# 1_0.net
KiCad netlist of a schematic drawn in EAGLE
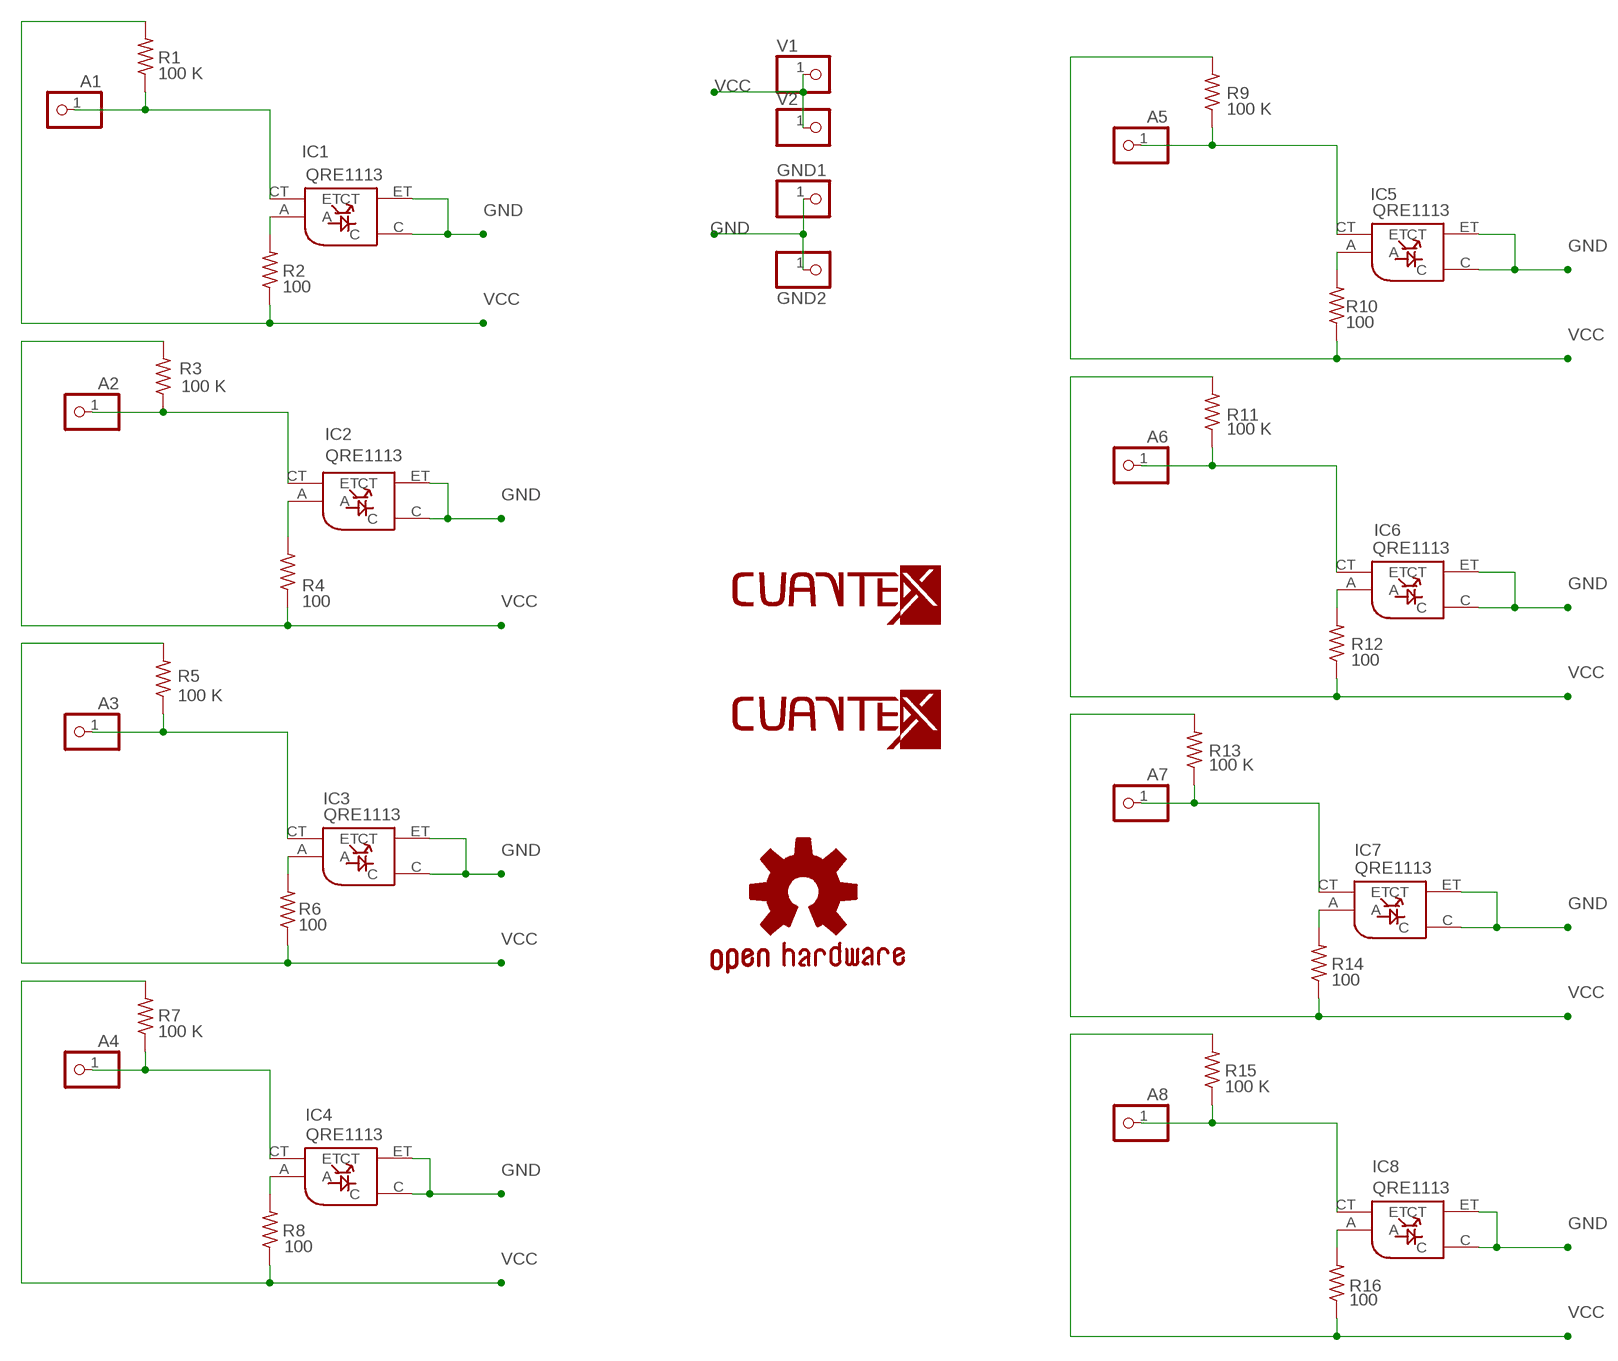
[diagram p0: schematic, sheet 1]

(export (version "E")
  (design (tool "Eeschema 10.0.6"))
  (components
    (comp (ref "A1")
      (value "PINHD-1X1")
      (footprint "eagle-import:1X01")
      (libsource (lib "eagle-import") (part "PINHD-1X1"))
    )
    (comp (ref "A2")
      (value "PINHD-1X1")
      (footprint "eagle-import:1X01")
      (libsource (lib "eagle-import") (part "PINHD-1X1"))
    )
    (comp (ref "A3")
      (value "PINHD-1X1")
      (footprint "eagle-import:1X01")
      (libsource (lib "eagle-import") (part "PINHD-1X1"))
    )
    (comp (ref "A4")
      (value "PINHD-1X1")
      (footprint "eagle-import:1X01")
      (libsource (lib "eagle-import") (part "PINHD-1X1"))
    )
    (comp (ref "A5")
      (value "PINHD-1X1")
      (footprint "eagle-import:1X01")
      (libsource (lib "eagle-import") (part "PINHD-1X1"))
    )
    (comp (ref "A6")
      (value "PINHD-1X1")
      (footprint "eagle-import:1X01")
      (libsource (lib "eagle-import") (part "PINHD-1X1"))
    )
    (comp (ref "A7")
      (value "PINHD-1X1")
      (footprint "eagle-import:1X01")
      (libsource (lib "eagle-import") (part "PINHD-1X1"))
    )
    (comp (ref "A8")
      (value "PINHD-1X1")
      (footprint "eagle-import:1X01")
      (libsource (lib "eagle-import") (part "PINHD-1X1"))
    )
    (comp (ref "GND1")
      (value "PINHD-1X1")
      (footprint "eagle-import:1X01")
      (libsource (lib "eagle-import") (part "PINHD-1X1"))
    )
    (comp (ref "GND2")
      (value "PINHD-1X1")
      (footprint "eagle-import:1X01")
      (libsource (lib "eagle-import") (part "PINHD-1X1"))
    )
    (comp (ref "GOLD_ORB_SM1")
      (value "OSHWLOGO_GOLD_ORB_SM")
      (footprint "eagle-import:OSHW2")
      (libsource (lib "eagle-import") (part "OSHWLOGO_GOLD_ORB_SM"))
    )
    (comp (ref "IC1")
      (value "QRE1113")
      (footprint "eagle-import:QRE1113")
      (libsource (lib "eagle-import") (part "QRE1113"))
    )
    (comp (ref "IC2")
      (value "QRE1113")
      (footprint "eagle-import:QRE1113")
      (libsource (lib "eagle-import") (part "QRE1113"))
    )
    (comp (ref "IC3")
      (value "QRE1113")
      (footprint "eagle-import:QRE1113")
      (libsource (lib "eagle-import") (part "QRE1113"))
    )
    (comp (ref "IC4")
      (value "QRE1113")
      (footprint "eagle-import:QRE1113")
      (libsource (lib "eagle-import") (part "QRE1113"))
    )
    (comp (ref "IC5")
      (value "QRE1113")
      (footprint "eagle-import:QRE1113")
      (libsource (lib "eagle-import") (part "QRE1113"))
    )
    (comp (ref "IC6")
      (value "QRE1113")
      (footprint "eagle-import:QRE1113")
      (libsource (lib "eagle-import") (part "QRE1113"))
    )
    (comp (ref "IC7")
      (value "QRE1113")
      (footprint "eagle-import:QRE1113")
      (libsource (lib "eagle-import") (part "QRE1113"))
    )
    (comp (ref "IC8")
      (value "QRE1113")
      (footprint "eagle-import:QRE1113")
      (libsource (lib "eagle-import") (part "QRE1113"))
    )
    (comp (ref "R1")
      (value "100 K")
      (footprint "eagle-import:R0603")
      (libsource (lib "eagle-import") (part "R-US_R0603"))
    )
    (comp (ref "R2")
      (value "100")
      (footprint "eagle-import:R0603")
      (libsource (lib "eagle-import") (part "R-US_R0603"))
    )
    (comp (ref "R3")
      (value "100 K")
      (footprint "eagle-import:R0603")
      (libsource (lib "eagle-import") (part "R-US_R0603"))
    )
    (comp (ref "R4")
      (value "100")
      (footprint "eagle-import:R0603")
      (libsource (lib "eagle-import") (part "R-US_R0603"))
    )
    (comp (ref "R5")
      (value "100 K")
      (footprint "eagle-import:R0603")
      (libsource (lib "eagle-import") (part "R-US_R0603"))
    )
    (comp (ref "R6")
      (value "100")
      (footprint "eagle-import:R0603")
      (libsource (lib "eagle-import") (part "R-US_R0603"))
    )
    (comp (ref "R7")
      (value "100 K")
      (footprint "eagle-import:R0603")
      (libsource (lib "eagle-import") (part "R-US_R0603"))
    )
    (comp (ref "R8")
      (value "100")
      (footprint "eagle-import:R0603")
      (libsource (lib "eagle-import") (part "R-US_R0603"))
    )
    (comp (ref "R9")
      (value "100 K")
      (footprint "eagle-import:R0603")
      (libsource (lib "eagle-import") (part "R-US_R0603"))
    )
    (comp (ref "R10")
      (value "100")
      (footprint "eagle-import:R0603")
      (libsource (lib "eagle-import") (part "R-US_R0603"))
    )
    (comp (ref "R11")
      (value "100 K")
      (footprint "eagle-import:R0603")
      (libsource (lib "eagle-import") (part "R-US_R0603"))
    )
    (comp (ref "R12")
      (value "100")
      (footprint "eagle-import:R0603")
      (libsource (lib "eagle-import") (part "R-US_R0603"))
    )
    (comp (ref "R13")
      (value "100 K")
      (footprint "eagle-import:R0603")
      (libsource (lib "eagle-import") (part "R-US_R0603"))
    )
    (comp (ref "R14")
      (value "100")
      (footprint "eagle-import:R0603")
      (libsource (lib "eagle-import") (part "R-US_R0603"))
    )
    (comp (ref "R15")
      (value "100 K")
      (footprint "eagle-import:R0603")
      (libsource (lib "eagle-import") (part "R-US_R0603"))
    )
    (comp (ref "R16")
      (value "100")
      (footprint "eagle-import:R0603")
      (libsource (lib "eagle-import") (part "R-US_R0603"))
    )
    (comp (ref "U$1")
      (value "LOGO-TOP-30MM")
      (footprint "eagle-import:C-1")
      (libsource (lib "eagle-import") (part "LOGO-TOP-30MM"))
    )
    (comp (ref "U$2")
      (value "LOGO-TOP-20MM")
      (footprint "eagle-import:C-0")
      (libsource (lib "eagle-import") (part "LOGO-TOP-20MM"))
    )
    (comp (ref "V1")
      (value "PINHD-1X1")
      (footprint "eagle-import:1X01")
      (libsource (lib "eagle-import") (part "PINHD-1X1"))
    )
    (comp (ref "V2")
      (value "PINHD-1X1")
      (footprint "eagle-import:1X01")
      (libsource (lib "eagle-import") (part "PINHD-1X1"))
    )
  )
  (nets
    (net (code "1") (name "/GND") (class "Default")
      (node (ref "GND1") (pin "1") (pinfunction "1_1") (pintype "passive"))
      (node (ref "GND2") (pin "1") (pinfunction "1_1") (pintype "passive"))
      (node (ref "IC1") (pin "C") (pinfunction "C_C") (pintype "bidirectional"))
      (node (ref "IC1") (pin "ET") (pinfunction "CT_ET") (pintype "bidirectional"))
      (node (ref "IC2") (pin "C") (pinfunction "C_C") (pintype "bidirectional"))
      (node (ref "IC2") (pin "ET") (pinfunction "CT_ET") (pintype "bidirectional"))
      (node (ref "IC3") (pin "C") (pinfunction "C_C") (pintype "bidirectional"))
      (node (ref "IC3") (pin "ET") (pinfunction "CT_ET") (pintype "bidirectional"))
      (node (ref "IC4") (pin "C") (pinfunction "C_C") (pintype "bidirectional"))
      (node (ref "IC4") (pin "ET") (pinfunction "CT_ET") (pintype "bidirectional"))
      (node (ref "IC5") (pin "C") (pinfunction "C_C") (pintype "bidirectional"))
      (node (ref "IC5") (pin "ET") (pinfunction "CT_ET") (pintype "bidirectional"))
      (node (ref "IC6") (pin "C") (pinfunction "C_C") (pintype "bidirectional"))
      (node (ref "IC6") (pin "ET") (pinfunction "CT_ET") (pintype "bidirectional"))
      (node (ref "IC7") (pin "C") (pinfunction "C_C") (pintype "bidirectional"))
      (node (ref "IC7") (pin "ET") (pinfunction "CT_ET") (pintype "bidirectional"))
      (node (ref "IC8") (pin "C") (pinfunction "C_C") (pintype "bidirectional"))
      (node (ref "IC8") (pin "ET") (pinfunction "CT_ET") (pintype "bidirectional"))
    )
    (net (code "2") (name "/VCC") (class "Default")
      (node (ref "R1") (pin "2") (pinfunction "2_2") (pintype "passive"))
      (node (ref "R10") (pin "1") (pinfunction "1_1") (pintype "passive"))
      (node (ref "R11") (pin "2") (pinfunction "2_2") (pintype "passive"))
      (node (ref "R12") (pin "1") (pinfunction "1_1") (pintype "passive"))
      (node (ref "R13") (pin "2") (pinfunction "2_2") (pintype "passive"))
      (node (ref "R14") (pin "1") (pinfunction "1_1") (pintype "passive"))
      (node (ref "R15") (pin "2") (pinfunction "2_2") (pintype "passive"))
      (node (ref "R16") (pin "1") (pinfunction "1_1") (pintype "passive"))
      (node (ref "R2") (pin "1") (pinfunction "1_1") (pintype "passive"))
      (node (ref "R3") (pin "2") (pinfunction "2_2") (pintype "passive"))
      (node (ref "R4") (pin "1") (pinfunction "1_1") (pintype "passive"))
      (node (ref "R5") (pin "2") (pinfunction "2_2") (pintype "passive"))
      (node (ref "R6") (pin "1") (pinfunction "1_1") (pintype "passive"))
      (node (ref "R7") (pin "2") (pinfunction "2_2") (pintype "passive"))
      (node (ref "R8") (pin "1") (pinfunction "1_1") (pintype "passive"))
      (node (ref "R9") (pin "2") (pinfunction "2_2") (pintype "passive"))
      (node (ref "V1") (pin "1") (pinfunction "1_1") (pintype "passive"))
      (node (ref "V2") (pin "1") (pinfunction "1_1") (pintype "passive"))
    )
    (net (code "3") (name "Net-(IC1-ET)") (class "Default")
      (node (ref "A1") (pin "1") (pinfunction "1_1") (pintype "passive"))
      (node (ref "IC1") (pin "CT") (pinfunction "ET_CT") (pintype "bidirectional"))
      (node (ref "R1") (pin "1") (pinfunction "1_1") (pintype "passive"))
    )
    (net (code "4") (name "Net-(IC1-PadA)") (class "Default")
      (node (ref "IC1") (pin "A") (pinfunction "A_A") (pintype "bidirectional"))
      (node (ref "R2") (pin "2") (pinfunction "2_2") (pintype "passive"))
    )
    (net (code "5") (name "Net-(IC2-ET)") (class "Default")
      (node (ref "A2") (pin "1") (pinfunction "1_1") (pintype "passive"))
      (node (ref "IC2") (pin "CT") (pinfunction "ET_CT") (pintype "bidirectional"))
      (node (ref "R3") (pin "1") (pinfunction "1_1") (pintype "passive"))
    )
    (net (code "6") (name "Net-(IC2-PadA)") (class "Default")
      (node (ref "IC2") (pin "A") (pinfunction "A_A") (pintype "bidirectional"))
      (node (ref "R4") (pin "2") (pinfunction "2_2") (pintype "passive"))
    )
    (net (code "7") (name "Net-(IC3-ET)") (class "Default")
      (node (ref "A3") (pin "1") (pinfunction "1_1") (pintype "passive"))
      (node (ref "IC3") (pin "CT") (pinfunction "ET_CT") (pintype "bidirectional"))
      (node (ref "R5") (pin "1") (pinfunction "1_1") (pintype "passive"))
    )
    (net (code "8") (name "Net-(IC3-PadA)") (class "Default")
      (node (ref "IC3") (pin "A") (pinfunction "A_A") (pintype "bidirectional"))
      (node (ref "R6") (pin "2") (pinfunction "2_2") (pintype "passive"))
    )
    (net (code "9") (name "Net-(IC4-ET)") (class "Default")
      (node (ref "A4") (pin "1") (pinfunction "1_1") (pintype "passive"))
      (node (ref "IC4") (pin "CT") (pinfunction "ET_CT") (pintype "bidirectional"))
      (node (ref "R7") (pin "1") (pinfunction "1_1") (pintype "passive"))
    )
    (net (code "10") (name "Net-(IC4-PadA)") (class "Default")
      (node (ref "IC4") (pin "A") (pinfunction "A_A") (pintype "bidirectional"))
      (node (ref "R8") (pin "2") (pinfunction "2_2") (pintype "passive"))
    )
    (net (code "11") (name "Net-(IC5-ET)") (class "Default")
      (node (ref "A5") (pin "1") (pinfunction "1_1") (pintype "passive"))
      (node (ref "IC5") (pin "CT") (pinfunction "ET_CT") (pintype "bidirectional"))
      (node (ref "R9") (pin "1") (pinfunction "1_1") (pintype "passive"))
    )
    (net (code "12") (name "Net-(IC5-PadA)") (class "Default")
      (node (ref "IC5") (pin "A") (pinfunction "A_A") (pintype "bidirectional"))
      (node (ref "R10") (pin "2") (pinfunction "2_2") (pintype "passive"))
    )
    (net (code "13") (name "Net-(IC6-ET)") (class "Default")
      (node (ref "A6") (pin "1") (pinfunction "1_1") (pintype "passive"))
      (node (ref "IC6") (pin "CT") (pinfunction "ET_CT") (pintype "bidirectional"))
      (node (ref "R11") (pin "1") (pinfunction "1_1") (pintype "passive"))
    )
    (net (code "14") (name "Net-(IC6-PadA)") (class "Default")
      (node (ref "IC6") (pin "A") (pinfunction "A_A") (pintype "bidirectional"))
      (node (ref "R12") (pin "2") (pinfunction "2_2") (pintype "passive"))
    )
    (net (code "15") (name "Net-(IC7-ET)") (class "Default")
      (node (ref "A7") (pin "1") (pinfunction "1_1") (pintype "passive"))
      (node (ref "IC7") (pin "CT") (pinfunction "ET_CT") (pintype "bidirectional"))
      (node (ref "R13") (pin "1") (pinfunction "1_1") (pintype "passive"))
    )
    (net (code "16") (name "Net-(IC7-PadA)") (class "Default")
      (node (ref "IC7") (pin "A") (pinfunction "A_A") (pintype "bidirectional"))
      (node (ref "R14") (pin "2") (pinfunction "2_2") (pintype "passive"))
    )
    (net (code "17") (name "Net-(IC8-ET)") (class "Default")
      (node (ref "A8") (pin "1") (pinfunction "1_1") (pintype "passive"))
      (node (ref "IC8") (pin "CT") (pinfunction "ET_CT") (pintype "bidirectional"))
      (node (ref "R15") (pin "1") (pinfunction "1_1") (pintype "passive"))
    )
    (net (code "18") (name "Net-(IC8-PadA)") (class "Default")
      (node (ref "IC8") (pin "A") (pinfunction "A_A") (pintype "bidirectional"))
      (node (ref "R16") (pin "2") (pinfunction "2_2") (pintype "passive"))
    )
  )
)
